# Alimentacion.net
KiCad netlist of a schematic drawn in Altium Designer
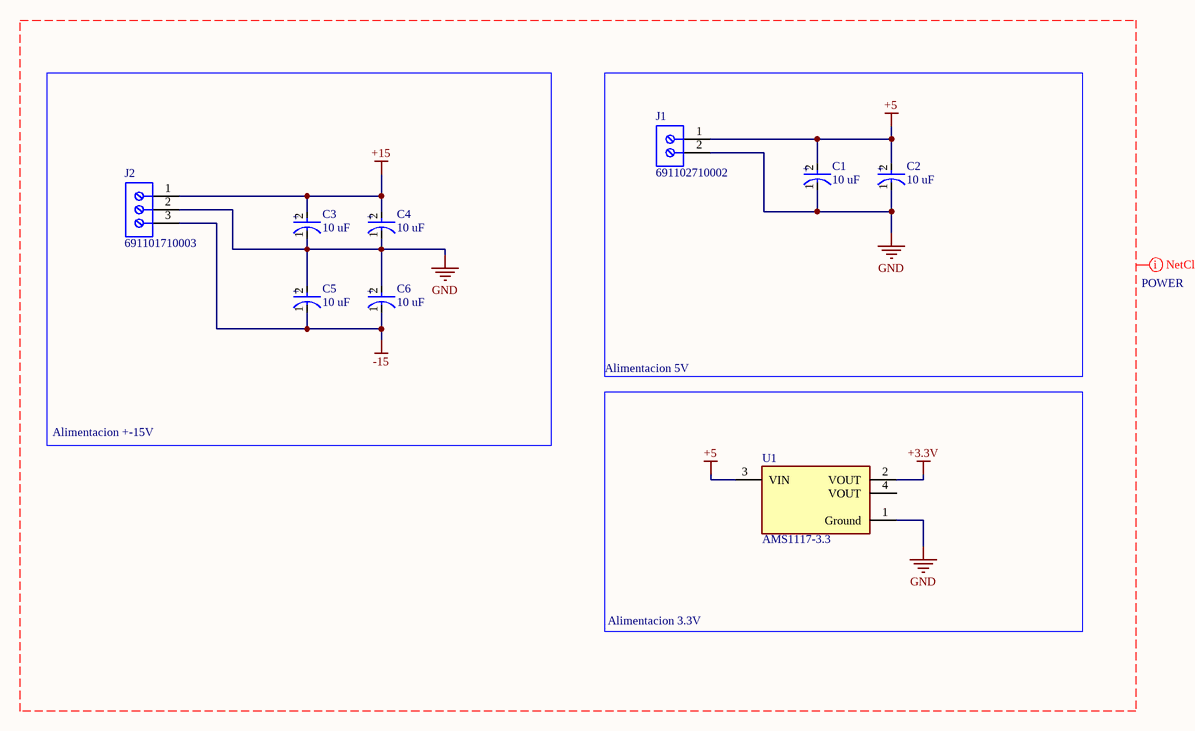
[diagram p0: Alimentacion.SchDoc]

(export (version "E")
  (design (tool "Eeschema 10.0.6"))
  (components
    (comp (ref "C1")
      (value "10 uF")
      (footprint "FP-RAD-TH-D_5_0_5-L_11_1-MFG")
      (description "Aluminum Electrolytic Capacitors (Radial Lead Type) 10uF ±20% 63V")
      (fields (field (name "TOLERANCE") "20%") (field (name "VOLTAGE") "63V"))
      (libsource (lib "Altium Content Vault") (part "a00bbbee19879c290e62620ae7e47b1"))
    )
    (comp (ref "C2")
      (value "10 uF")
      (footprint "FP-RAD-TH-D_5_0_5-L_11_1-MFG")
      (description "Aluminum Electrolytic Capacitors (Radial Lead Type) 10uF ±20% 63V")
      (fields (field (name "TOLERANCE") "20%") (field (name "VOLTAGE") "63V"))
      (libsource (lib "Altium Content Vault") (part "a00bbbee19879c290e62620ae7e47b1"))
    )
    (comp (ref "C3")
      (value "10 uF")
      (footprint "FP-RAD-TH-D_5_0_5-L_11_1-MFG")
      (description "Aluminum Electrolytic Capacitors (Radial Lead Type) 10uF ±20% 63V")
      (fields (field (name "TOLERANCE") "20%") (field (name "VOLTAGE") "63V"))
      (libsource (lib "Altium Content Vault") (part "a00bbbee19879c290e62620ae7e47b1"))
    )
    (comp (ref "C4")
      (value "10 uF")
      (footprint "FP-RAD-TH-D_5_0_5-L_11_1-MFG")
      (description "Aluminum Electrolytic Capacitors (Radial Lead Type) 10uF ±20% 63V")
      (fields (field (name "TOLERANCE") "20%") (field (name "VOLTAGE") "63V"))
      (libsource (lib "Altium Content Vault") (part "a00bbbee19879c290e62620ae7e47b1"))
    )
    (comp (ref "C5")
      (value "10 uF")
      (footprint "FP-RAD-TH-D_5_0_5-L_11_1-MFG")
      (description "Aluminum Electrolytic Capacitors (Radial Lead Type) 10uF ±20% 63V")
      (fields (field (name "TOLERANCE") "20%") (field (name "VOLTAGE") "63V"))
      (libsource (lib "Altium Content Vault") (part "a00bbbee19879c290e62620ae7e47b1"))
    )
    (comp (ref "C6")
      (value "10 uF")
      (footprint "FP-RAD-TH-D_5_0_5-L_11_1-MFG")
      (description "Aluminum Electrolytic Capacitors (Radial Lead Type) 10uF ±20% 63V")
      (fields (field (name "TOLERANCE") "20%") (field (name "VOLTAGE") "63V"))
      (libsource (lib "Altium Content Vault") (part "a00bbbee19879c290e62620ae7e47b1"))
    )
    (comp (ref "J1")
      (value "691102710002")
      (footprint "691102710002")
      (fields (field (name "VOLTAGE") "300V"))
      (libsource (lib "Altium Content Vault") (part "TBL - 1R - 02P - Screw"))
    )
    (comp (ref "J2")
      (value "691101710003")
      (footprint "691101710003")
      (fields (field (name "VOLTAGE") "250V"))
      (libsource (lib "Altium Content Vault") (part "TBL - 1R - 03P - Screw"))
    )
    (comp (ref "U1")
      (value "AMS1117-3.3")
      (footprint "FP-AMS1117-IPC_C")
      (description "LDO Voltage Regulators 1A, 3.3V")
      (fields
        (field (name "OCTOPART") "https://octopart.com/ams1117-3.3-advanced+monolithic+systems-25899300")
        (field (name "MANUFACTURER") "Advanced Monolithic Systems")
      )
      (libsource (lib "Altium Content Vault") (part "8bdbb5f8e77002000e30dd2845d0354"))
    )
  )
  (nets
    (net (code "1") (name "+3.3V") (class "Default")
      (node (ref "U1") (pin "2") (pinfunction "VOUT_2") (pintype "passive"))
    )
    (net (code "2") (name "+5") (class "Default")
      (node (ref "C1") (pin "2") (pinfunction "A_2") (pintype "passive"))
      (node (ref "C2") (pin "2") (pinfunction "A_2") (pintype "passive"))
      (node (ref "J1") (pin "1") (pinfunction "1_1") (pintype "passive"))
      (node (ref "U1") (pin "3") (pinfunction "VIN_3") (pintype "power_in"))
    )
    (net (code "3") (name "+15") (class "Default")
      (node (ref "C3") (pin "2") (pinfunction "A_2") (pintype "passive"))
      (node (ref "C4") (pin "2") (pinfunction "A_2") (pintype "passive"))
      (node (ref "J2") (pin "1") (pinfunction "1_1") (pintype "passive"))
    )
    (net (code "4") (name "-15") (class "Default")
      (node (ref "C5") (pin "1") (pinfunction "C_1") (pintype "passive"))
      (node (ref "C6") (pin "1") (pinfunction "C_1") (pintype "passive"))
      (node (ref "J2") (pin "3") (pinfunction "3_3") (pintype "passive"))
    )
    (net (code "5") (name "GND") (class "Default")
      (node (ref "C1") (pin "1") (pinfunction "C_1") (pintype "passive"))
      (node (ref "C2") (pin "1") (pinfunction "C_1") (pintype "passive"))
      (node (ref "C3") (pin "1") (pinfunction "C_1") (pintype "passive"))
      (node (ref "C4") (pin "1") (pinfunction "C_1") (pintype "passive"))
      (node (ref "C5") (pin "2") (pinfunction "A_2") (pintype "passive"))
      (node (ref "C6") (pin "2") (pinfunction "A_2") (pintype "passive"))
      (node (ref "J1") (pin "2") (pinfunction "2_2") (pintype "passive"))
      (node (ref "J2") (pin "2") (pinfunction "2_2") (pintype "passive"))
      (node (ref "U1") (pin "1") (pinfunction "Ground_1") (pintype "power_in"))
    )
    (net (code "6") (name "unconnected-(U1-VOUT-Pad4)") (class "Default")
      (node (ref "U1") (pin "4") (pinfunction "VOUT_4") (pintype "passive"))
    )
  )
)
